# Micro_SD-Card_USB2_0.net
KiCad netlist of a schematic drawn in Altium Designer
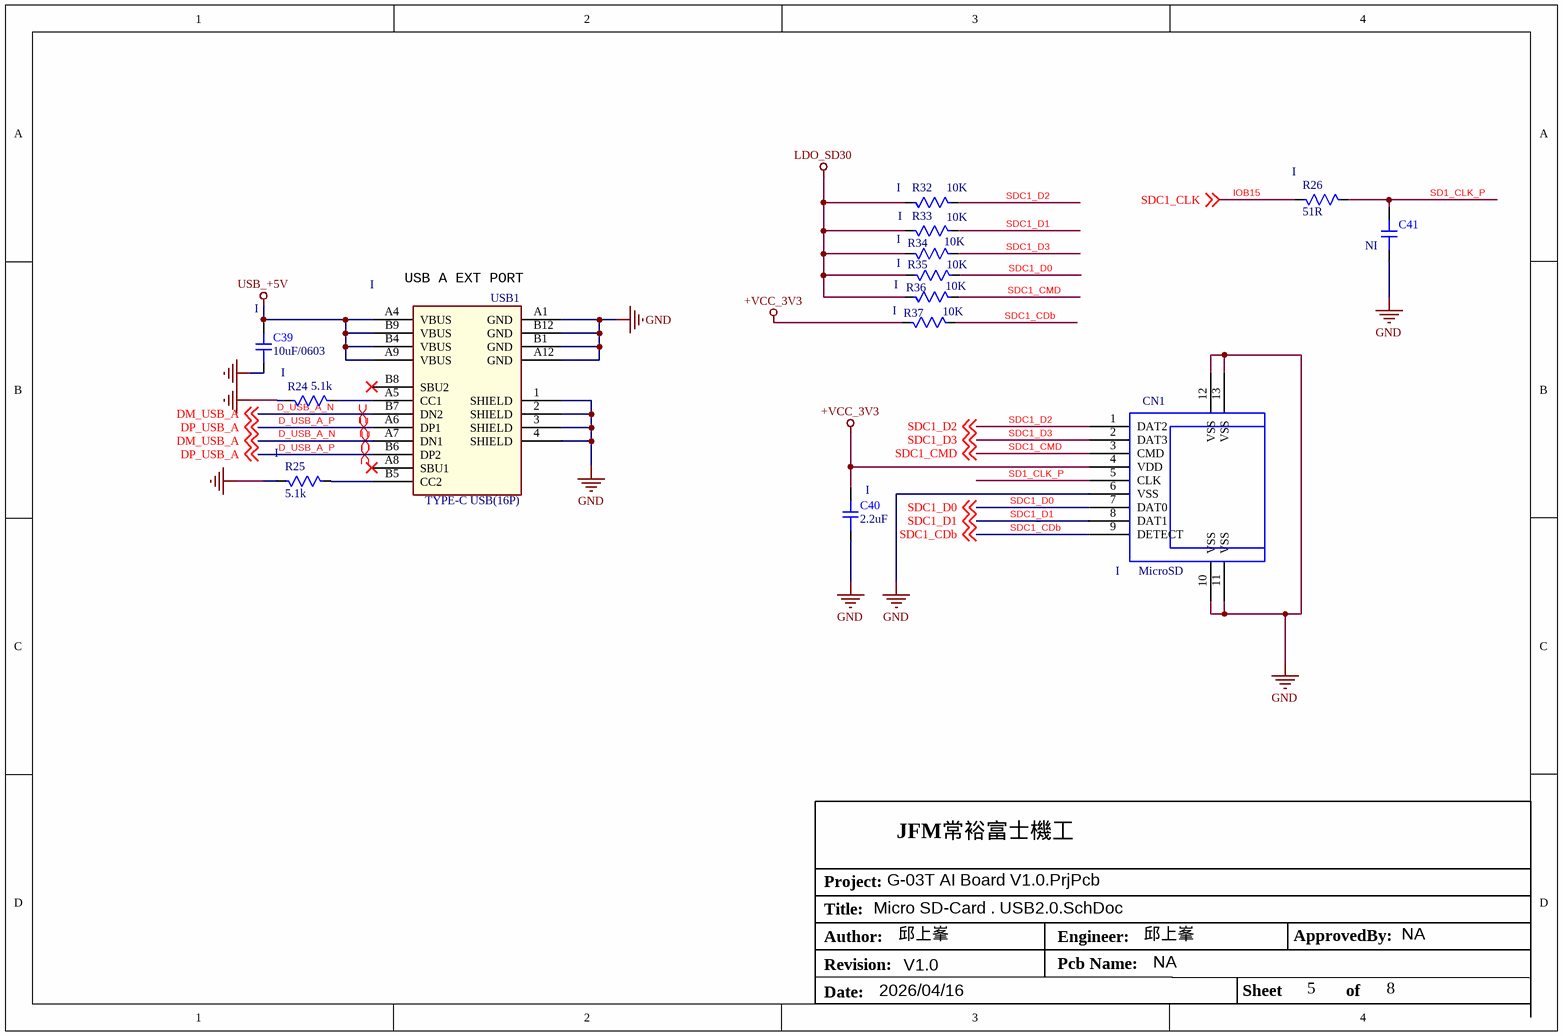
[diagram p0: Micro SD-Card . USB2.0.SchDoc]

(export (version "E")
  (design (tool "Eeschema 10.0.6"))
  (components
    (comp (ref "C39")
      (value "10uF/0603")
      (footprint "C0603")
      (fields (field (name "BOM") "I"))
      (libsource (lib "AMIDA7") (part "Cap"))
    )
    (comp (ref "C40")
      (value "2.2uF")
      (footprint "C0402")
      (fields (field (name "BOM") "I"))
      (libsource (lib "AMIDA7") (part "Cap"))
    )
    (comp (ref "C41")
      (value "NI")
      (footprint "C0402")
      (fields (field (name "BOM") "NI"))
      (libsource (lib "AMIDA7") (part "Cap"))
    )
    (comp (ref "CN1")
      (value "MicroSD")
      (footprint "MicroSD")
      (fields (field (name "BOM") "I"))
      (libsource (lib "AMIDA7") (part "MicroSD"))
    )
    (comp (ref "R24")
      (value "5.1k")
      (footprint "R0603")
      (fields (field (name "BOM") "I"))
      (libsource (lib "AMIDA7") (part "Res"))
    )
    (comp (ref "R25")
      (value "5.1k")
      (footprint "R0603")
      (fields (field (name "BOM") "I"))
      (libsource (lib "AMIDA7") (part "Res"))
    )
    (comp (ref "R26")
      (value "51R")
      (footprint "R0603")
      (fields (field (name "BOM") "I"))
      (libsource (lib "AMIDA7") (part "Res"))
    )
    (comp (ref "R32")
      (value "10K")
      (footprint "R0402")
      (fields (field (name "BOM") "I"))
      (libsource (lib "AMIDA7") (part "Res"))
    )
    (comp (ref "R33")
      (value "10K")
      (footprint "R0402")
      (fields (field (name "BOM") "I"))
      (libsource (lib "AMIDA7") (part "Res"))
    )
    (comp (ref "R34")
      (value "10K")
      (footprint "R0402")
      (fields (field (name "BOM") "I"))
      (libsource (lib "AMIDA7") (part "Res"))
    )
    (comp (ref "R35")
      (value "10K")
      (footprint "R0402")
      (fields (field (name "BOM") "I"))
      (libsource (lib "AMIDA7") (part "Res"))
    )
    (comp (ref "R36")
      (value "10K")
      (footprint "R0402")
      (fields (field (name "BOM") "I"))
      (libsource (lib "AMIDA7") (part "Res"))
    )
    (comp (ref "R37")
      (value "10K")
      (footprint "R0402")
      (fields (field (name "BOM") "I"))
      (libsource (lib "AMIDA7") (part "Res"))
    )
    (comp (ref "USB1")
      (value "TYPE-C USB(16P)")
      (footprint "Type C USB (16P)")
      (description "CUC006AHP-BPIN")
      (fields (field (name "BOM") "I"))
      (libsource (lib "AMIDA7") (part "TYPE-C USB_1"))
    )
  )
  (nets
    (net (code "1") (name "+VCC_3V3") (class "Default")
      (node (ref "C40") (pin "2") (pinfunction "2_2") (pintype "passive"))
      (node (ref "CN1") (pin "4") (pinfunction "VDD_4") (pintype "passive"))
      (node (ref "R37") (pin "1") (pinfunction "1_1") (pintype "passive"))
    )
    (net (code "2") (name "/SD1_CLK_P") (class "Default")
      (node (ref "C41") (pin "2") (pinfunction "2_2") (pintype "passive"))
      (node (ref "CN1") (pin "5") (pinfunction "CLK_5") (pintype "passive"))
      (node (ref "R26") (pin "2") (pinfunction "2_2") (pintype "passive"))
    )
    (net (code "3") (name "DM_USB_A") (class "Default")
      (node (ref "USB1") (pin "A7") (pinfunction "DN1_A7") (pintype "passive"))
      (node (ref "USB1") (pin "B7") (pinfunction "DN2_B7") (pintype "passive"))
    )
    (net (code "4") (name "DP_USB_A") (class "Default")
      (node (ref "USB1") (pin "A6") (pinfunction "DP1_A6") (pintype "passive"))
      (node (ref "USB1") (pin "B6") (pinfunction "DP2_B6") (pintype "passive"))
    )
    (net (code "5") (name "GND") (class "Default")
      (node (ref "C39") (pin "1") (pinfunction "1_1") (pintype "passive"))
      (node (ref "C40") (pin "1") (pinfunction "1_1") (pintype "passive"))
      (node (ref "C41") (pin "1") (pinfunction "1_1") (pintype "passive"))
      (node (ref "CN1") (pin "10") (pinfunction "VSS_10") (pintype "passive"))
      (node (ref "CN1") (pin "11") (pinfunction "VSS_11") (pintype "passive"))
      (node (ref "CN1") (pin "12") (pinfunction "VSS_12") (pintype "passive"))
      (node (ref "CN1") (pin "13") (pinfunction "VSS_13") (pintype "passive"))
      (node (ref "CN1") (pin "6") (pinfunction "VSS_6") (pintype "passive"))
      (node (ref "R24") (pin "1") (pinfunction "1_1") (pintype "passive"))
      (node (ref "R25") (pin "1") (pinfunction "1_1") (pintype "passive"))
      (node (ref "USB1") (pin "1") (pinfunction "SHIELD_1") (pintype "passive"))
      (node (ref "USB1") (pin "2") (pinfunction "SHIELD_2") (pintype "passive"))
      (node (ref "USB1") (pin "3") (pinfunction "SHIELD_3") (pintype "passive"))
      (node (ref "USB1") (pin "4") (pinfunction "SHIELD_4") (pintype "passive"))
      (node (ref "USB1") (pin "A1") (pinfunction "GND_A1") (pintype "passive"))
      (node (ref "USB1") (pin "A12") (pinfunction "GND_A12") (pintype "passive"))
      (node (ref "USB1") (pin "B1") (pinfunction "GND_B1") (pintype "passive"))
      (node (ref "USB1") (pin "B12") (pinfunction "GND_B12") (pintype "passive"))
    )
    (net (code "6") (name "LDO_SD30") (class "Default")
      (node (ref "R32") (pin "1") (pinfunction "1_1") (pintype "passive"))
      (node (ref "R33") (pin "1") (pinfunction "1_1") (pintype "passive"))
      (node (ref "R34") (pin "1") (pinfunction "1_1") (pintype "passive"))
      (node (ref "R35") (pin "1") (pinfunction "1_1") (pintype "passive"))
      (node (ref "R36") (pin "1") (pinfunction "1_1") (pintype "passive"))
    )
    (net (code "7") (name "Net-(USB1-CC1)") (class "Default")
      (node (ref "R24") (pin "2") (pinfunction "2_2") (pintype "passive"))
      (node (ref "USB1") (pin "A5") (pinfunction "CC1_A5") (pintype "passive"))
    )
    (net (code "8") (name "Net-(USB1-CC2)") (class "Default")
      (node (ref "R25") (pin "2") (pinfunction "2_2") (pintype "passive"))
      (node (ref "USB1") (pin "B5") (pinfunction "CC2_B5") (pintype "passive"))
    )
    (net (code "9") (name "SDC1_CDb") (class "Default")
      (node (ref "CN1") (pin "9") (pinfunction "DETECT_9") (pintype "passive"))
      (node (ref "R37") (pin "2") (pinfunction "2_2") (pintype "passive"))
    )
    (net (code "10") (name "SDC1_CLK") (class "Default")
      (node (ref "R26") (pin "1") (pinfunction "1_1") (pintype "passive"))
    )
    (net (code "11") (name "SDC1_CMD") (class "Default")
      (node (ref "CN1") (pin "3") (pinfunction "CMD_3") (pintype "passive"))
      (node (ref "R36") (pin "2") (pinfunction "2_2") (pintype "passive"))
    )
    (net (code "12") (name "SDC1_D0") (class "Default")
      (node (ref "CN1") (pin "7") (pinfunction "DAT0_7") (pintype "passive"))
      (node (ref "R35") (pin "2") (pinfunction "2_2") (pintype "passive"))
    )
    (net (code "13") (name "SDC1_D1") (class "Default")
      (node (ref "CN1") (pin "8") (pinfunction "DAT1_8") (pintype "passive"))
      (node (ref "R33") (pin "2") (pinfunction "2_2") (pintype "passive"))
    )
    (net (code "14") (name "SDC1_D2") (class "Default")
      (node (ref "CN1") (pin "1") (pinfunction "DAT2_1") (pintype "passive"))
      (node (ref "R32") (pin "2") (pinfunction "2_2") (pintype "passive"))
    )
    (net (code "15") (name "SDC1_D3") (class "Default")
      (node (ref "CN1") (pin "2") (pinfunction "DAT3_2") (pintype "passive"))
      (node (ref "R34") (pin "2") (pinfunction "2_2") (pintype "passive"))
    )
    (net (code "16") (name "USB_+5V") (class "Default")
      (node (ref "C39") (pin "2") (pinfunction "2_2") (pintype "passive"))
      (node (ref "USB1") (pin "A4") (pinfunction "VBUS_A4") (pintype "passive"))
      (node (ref "USB1") (pin "A9") (pinfunction "VBUS_A9") (pintype "passive"))
      (node (ref "USB1") (pin "B4") (pinfunction "VBUS_B4") (pintype "passive"))
      (node (ref "USB1") (pin "B9") (pinfunction "VBUS_B9") (pintype "passive"))
    )
    (net (code "17") (name "unconnected-(USB1-SBU1-PadA8)") (class "Default")
      (node (ref "USB1") (pin "A8") (pinfunction "SBU1_A8") (pintype "passive"))
    )
    (net (code "18") (name "unconnected-(USB1-SBU2-PadB8)") (class "Default")
      (node (ref "USB1") (pin "B8") (pinfunction "SBU2_B8") (pintype "passive"))
    )
  )
)
